# SCH_VS_ALPHA_2024-07-11.net
KiCad netlist of a schematic drawn in EasyEDA
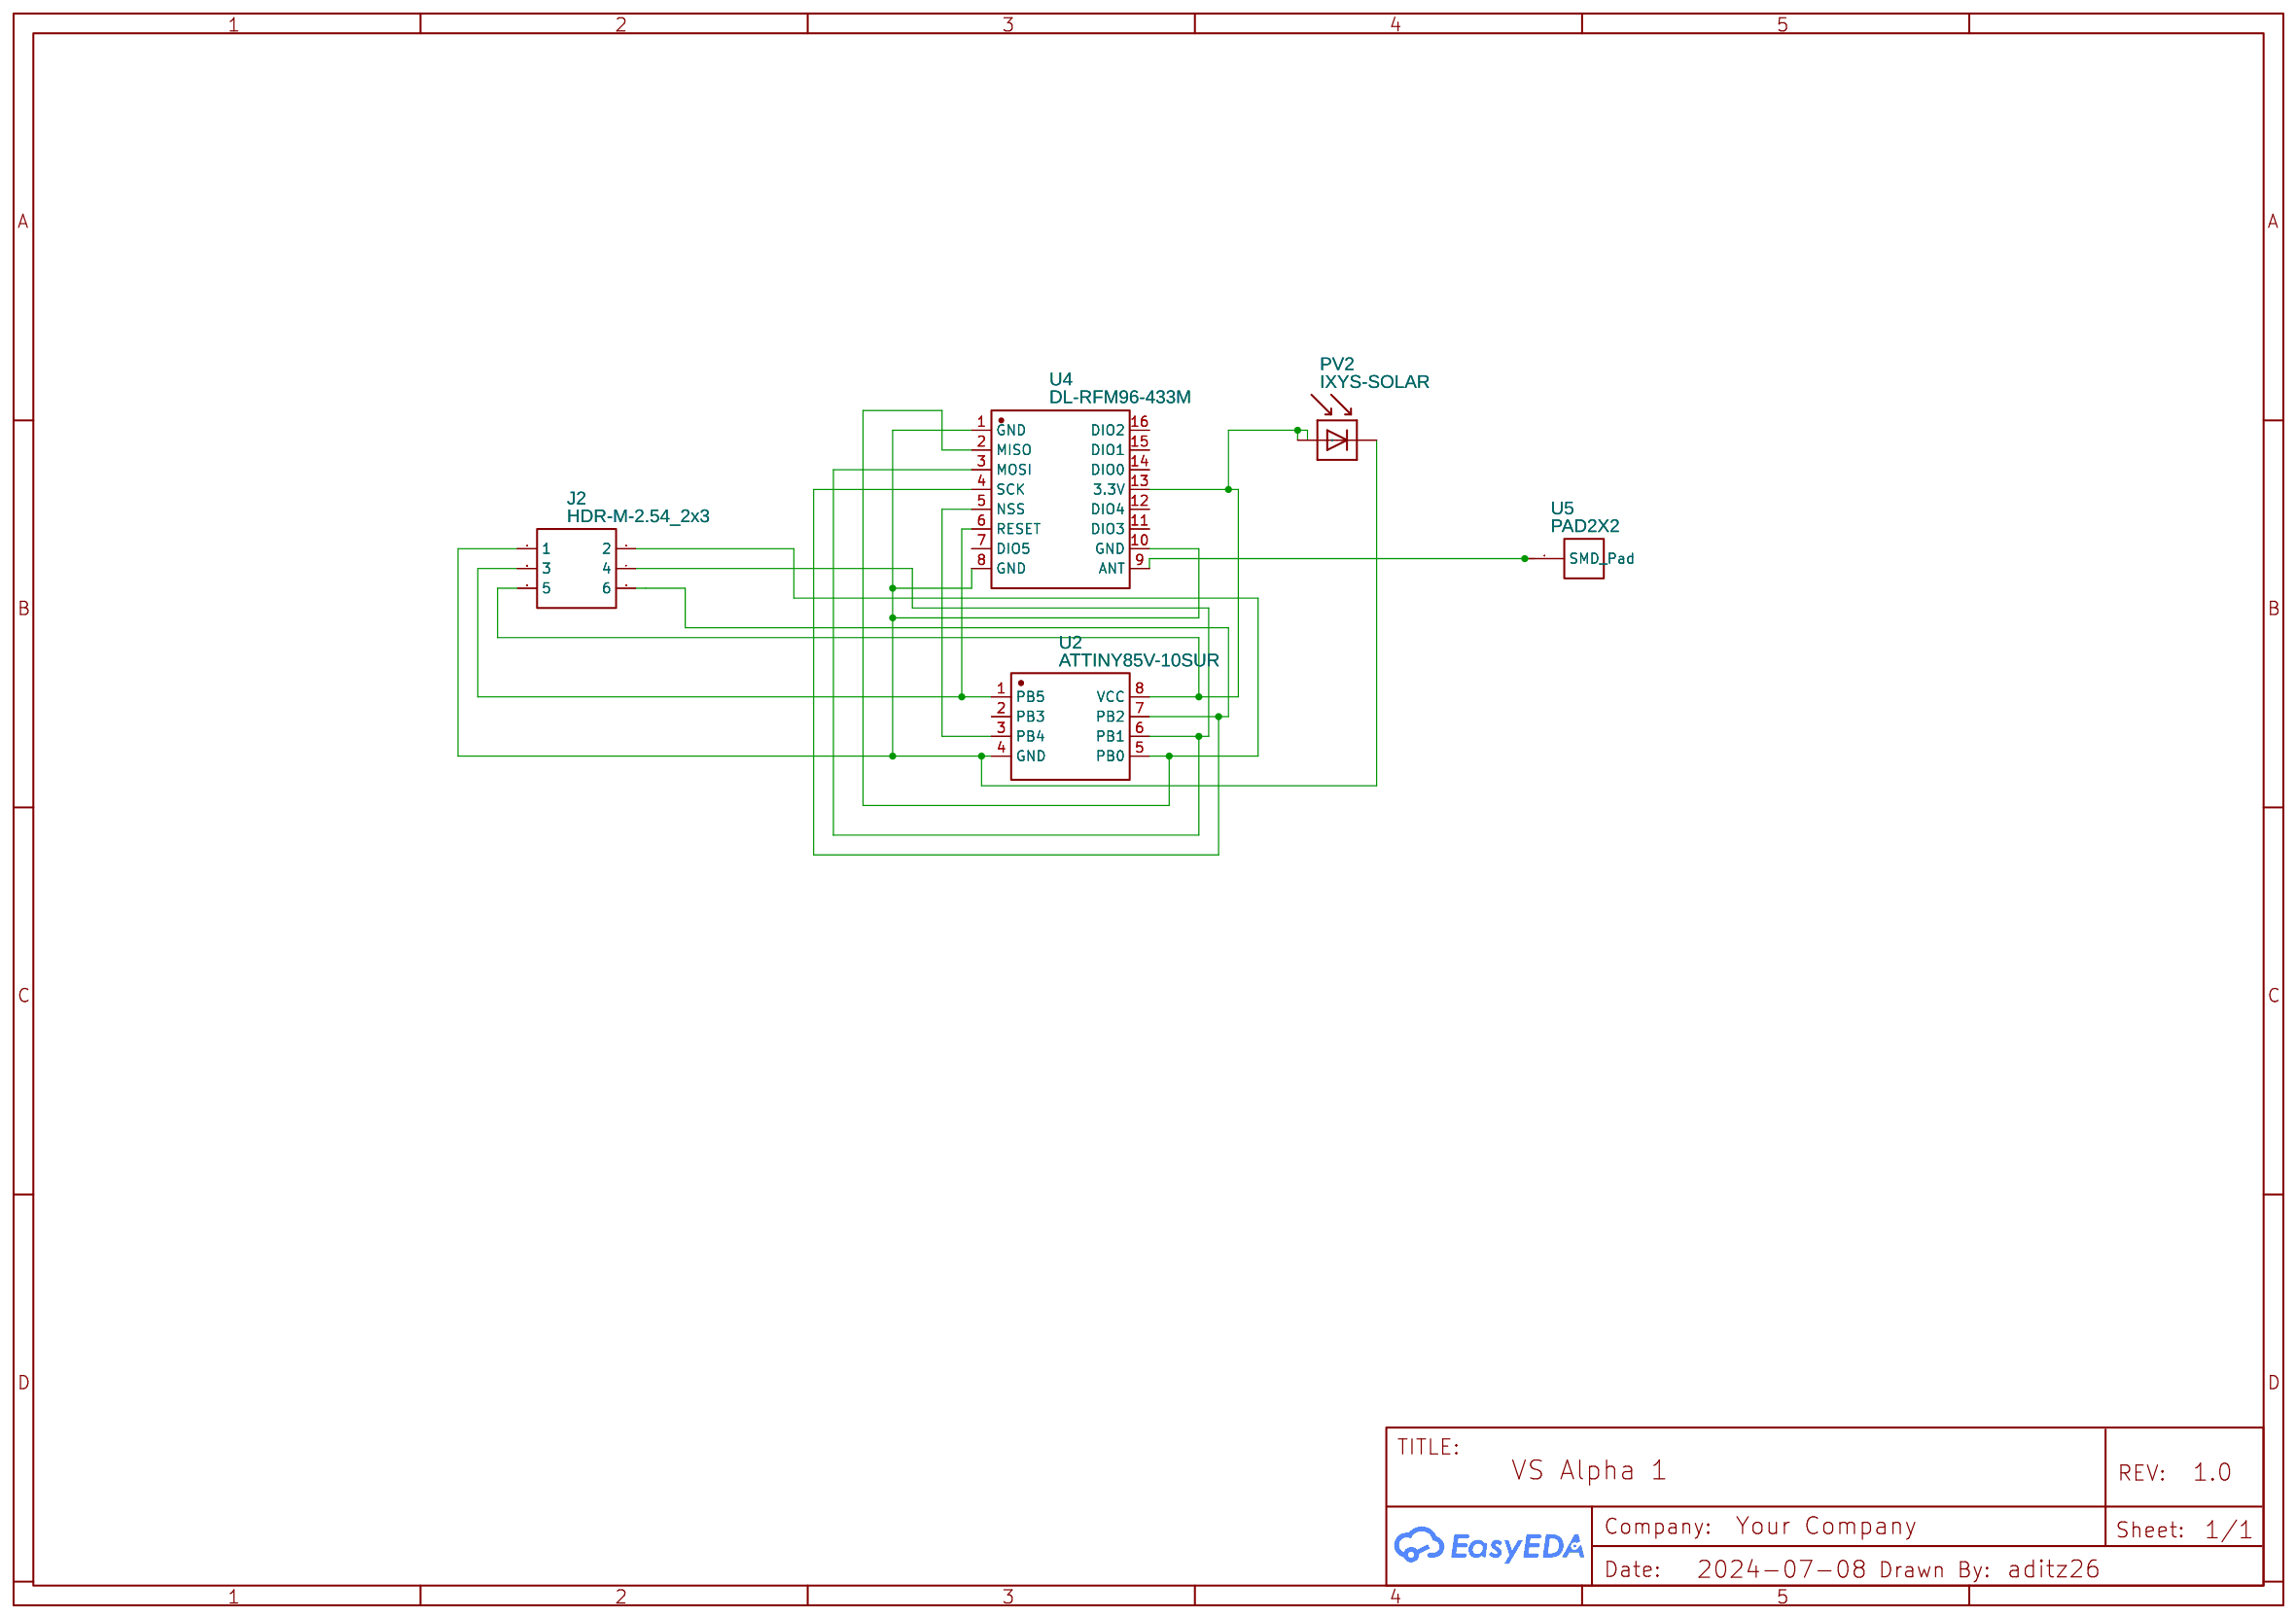
[diagram p0: schematic sheet]

(export (version "E")
  (design (tool "Eeschema 10.0.6"))
  (components
    (comp (ref "J2") (value "HDR-M-2.54_2x3") (libsource (lib "") (part "HDR-M-2.54_2x3")))
    (comp (ref "PV2") (value "IXYS-SOLAR") (libsource (lib "") (part "IXYS-SOLAR")))
    (comp (ref "U2")
      (value "ATTINY85V-10SUR")
      (fields (field (name "Manufacturer") "MICROCHIP(美国微芯)"))
      (libsource (lib "") (part "ATTINY85V-10SUR"))
    )
    (comp (ref "U4")
      (value "DL-RFM96-433M")
      (fields (field (name "Manufacturer") "DreamLNK(骏晔科技)"))
      (libsource (lib "") (part "DL-RFM96-433M"))
    )
    (comp (ref "U5") (value "PAD2X2") (libsource (lib "") (part "PAD2X2")))
  )
  (nets
    (net (code "1") (name "Net-(PV2-A)") (class "Default")
      (node (ref "J2") (pin "5") (pinfunction "5_5") (pintype "input"))
      (node (ref "PV2") (pin "+") (pinfunction "A_+") (pintype "unspecified"))
      (node (ref "U2") (pin "8") (pinfunction "VCC_8") (pintype "unspecified"))
      (node (ref "U4") (pin "13") (pinfunction "3.3V_13") (pintype "unspecified"))
    )
    (net (code "2") (name "Net-(PV2-C)") (class "Default")
      (node (ref "J2") (pin "1") (pinfunction "1_1") (pintype "input"))
      (node (ref "PV2") (pin "-") (pinfunction "C_-") (pintype "unspecified"))
      (node (ref "U2") (pin "4") (pinfunction "GND_4") (pintype "unspecified"))
      (node (ref "U4") (pin "1") (pinfunction "GND_1") (pintype "unspecified"))
      (node (ref "U4") (pin "10") (pinfunction "GND_10") (pintype "unspecified"))
      (node (ref "U4") (pin "8") (pinfunction "GND_8") (pintype "unspecified"))
    )
    (net (code "3") (name "Net-(U2-PB0)") (class "Default")
      (node (ref "J2") (pin "2") (pinfunction "2_2") (pintype "input"))
      (node (ref "U2") (pin "5") (pinfunction "PB0_5") (pintype "unspecified"))
      (node (ref "U4") (pin "2") (pinfunction "MISO_2") (pintype "unspecified"))
    )
    (net (code "4") (name "Net-(U2-PB1)") (class "Default")
      (node (ref "J2") (pin "4") (pinfunction "4_4") (pintype "input"))
      (node (ref "U2") (pin "6") (pinfunction "PB1_6") (pintype "unspecified"))
      (node (ref "U4") (pin "3") (pinfunction "MOSI_3") (pintype "unspecified"))
    )
    (net (code "5") (name "Net-(U2-PB2)") (class "Default")
      (node (ref "J2") (pin "6") (pinfunction "6_6") (pintype "input"))
      (node (ref "U2") (pin "7") (pinfunction "PB2_7") (pintype "unspecified"))
      (node (ref "U4") (pin "4") (pinfunction "SCK_4") (pintype "unspecified"))
    )
    (net (code "6") (name "Net-(U2-PB4)") (class "Default")
      (node (ref "U2") (pin "3") (pinfunction "PB4_3") (pintype "unspecified"))
      (node (ref "U4") (pin "5") (pinfunction "NSS_5") (pintype "unspecified"))
    )
    (net (code "7") (name "Net-(U2-PB5)") (class "Default")
      (node (ref "J2") (pin "3") (pinfunction "3_3") (pintype "input"))
      (node (ref "U2") (pin "1") (pinfunction "PB5_1") (pintype "unspecified"))
      (node (ref "U4") (pin "6") (pinfunction "RESET_6") (pintype "unspecified"))
    )
    (net (code "8") (name "Net-(U4-ANT)") (class "Default")
      (node (ref "U4") (pin "9") (pinfunction "ANT_9") (pintype "unspecified"))
      (node (ref "U5") (pin "1") (pinfunction "SMD_Pad_1") (pintype "unspecified"))
    )
    (net (code "9") (name "unconnected-(U2-PB3-Pad2)") (class "Default")
      (node (ref "U2") (pin "2") (pinfunction "PB3_2") (pintype "unspecified"))
    )
    (net (code "10") (name "unconnected-(U4-DIO0-Pad14)") (class "Default")
      (node (ref "U4") (pin "14") (pinfunction "DIO0_14") (pintype "unspecified"))
    )
    (net (code "11") (name "unconnected-(U4-DIO1-Pad15)") (class "Default")
      (node (ref "U4") (pin "15") (pinfunction "DIO1_15") (pintype "unspecified"))
    )
    (net (code "12") (name "unconnected-(U4-DIO2-Pad16)") (class "Default")
      (node (ref "U4") (pin "16") (pinfunction "DIO2_16") (pintype "unspecified"))
    )
    (net (code "13") (name "unconnected-(U4-DIO3-Pad11)") (class "Default")
      (node (ref "U4") (pin "11") (pinfunction "DIO3_11") (pintype "unspecified"))
    )
    (net (code "14") (name "unconnected-(U4-DIO4-Pad12)") (class "Default")
      (node (ref "U4") (pin "12") (pinfunction "DIO4_12") (pintype "unspecified"))
    )
    (net (code "15") (name "unconnected-(U4-DIO5-Pad7)") (class "Default")
      (node (ref "U4") (pin "7") (pinfunction "DIO5_7") (pintype "unspecified"))
    )
  )
)
